# SW3203.net
KiCad netlist of a schematic drawn in Altium Designer
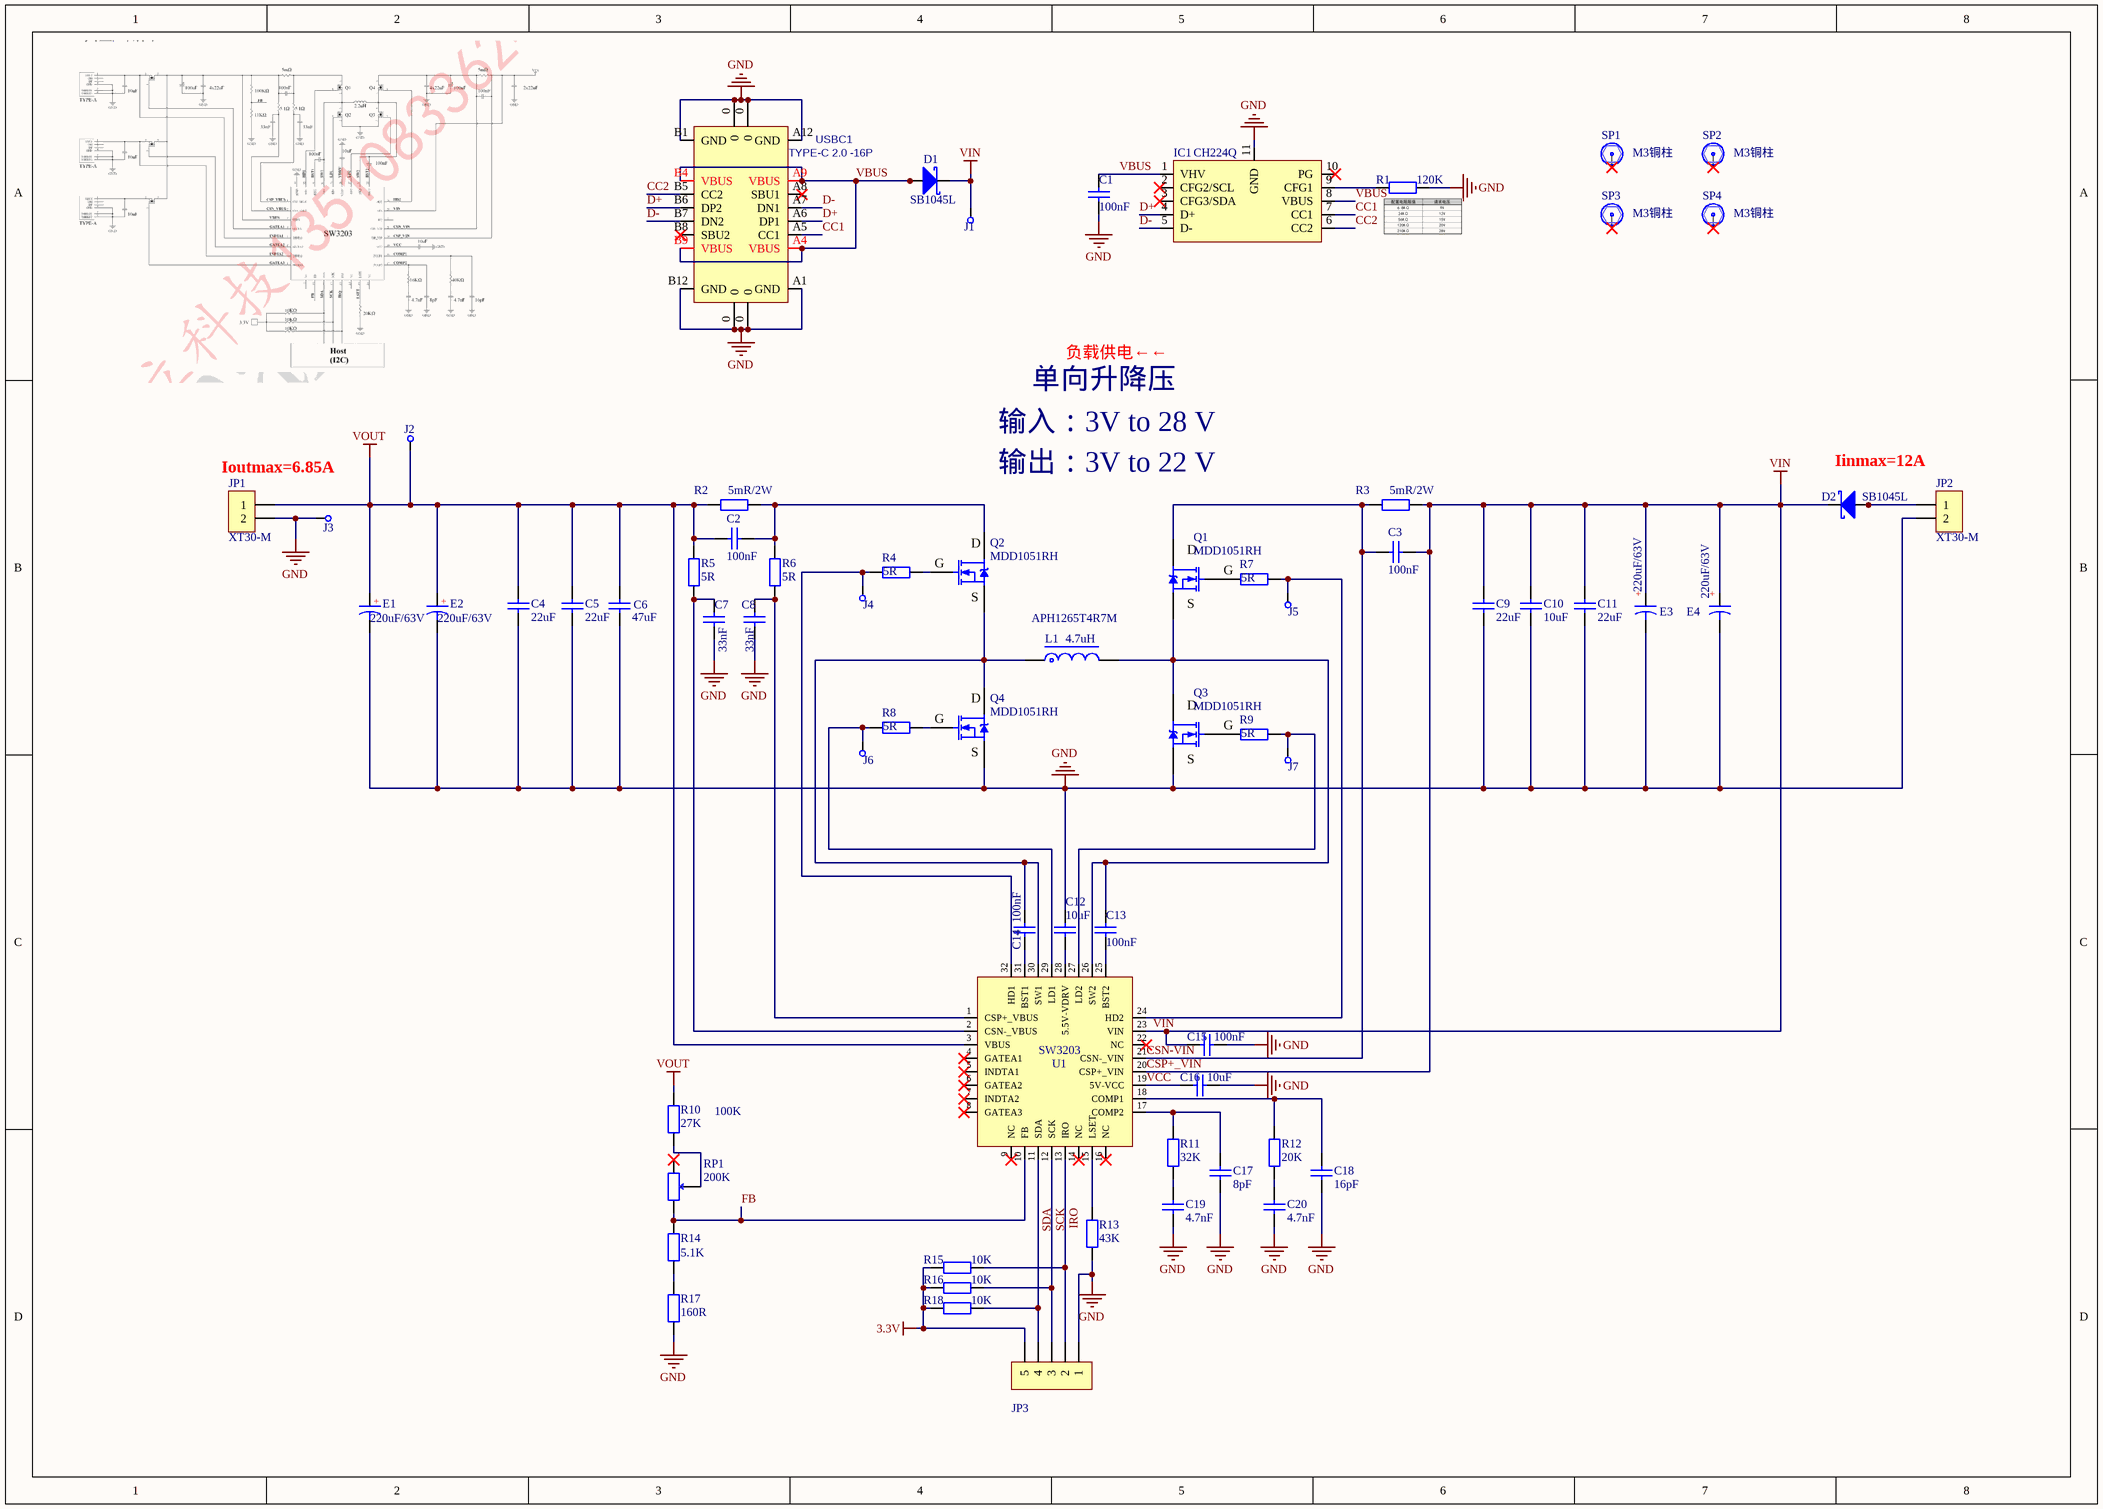
[diagram p0: SW3203.SchDoc]

(export (version "E")
  (design (tool "Eeschema 10.0.6"))
  (components
    (comp (ref "C1")
      (value "100nF")
      (footprint "C0805_L")
      (description "贴片电容/MLCC电容")
      (libsource (lib "0.1 - 电阻-电容-电感-保险丝-晶振-晶体-磁珠-电位器-法拉电容-馈通电容") (part "C"))
    )
    (comp (ref "C2")
      (value "100nF")
      (footprint "C0805_L")
      (description "贴片电容/MLCC电容")
      (libsource (lib "0.1 - 电阻-电容-电感-保险丝-晶振-晶体-磁珠-电位器-法拉电容-馈通电容") (part "C"))
    )
    (comp (ref "C3")
      (value "100nF")
      (footprint "C0805_L")
      (description "贴片电容/MLCC电容")
      (libsource (lib "0.1 - 电阻-电容-电感-保险丝-晶振-晶体-磁珠-电位器-法拉电容-馈通电容") (part "C"))
    )
    (comp (ref "C4")
      (value "22uF")
      (footprint "C0805_L")
      (description "贴片电容/MLCC电容")
      (libsource (lib "0.1 - 电阻-电容-电感-保险丝-晶振-晶体-磁珠-电位器-法拉电容-馈通电容") (part "C"))
    )
    (comp (ref "C5")
      (value "22uF")
      (footprint "C0805_L")
      (description "贴片电容/MLCC电容")
      (libsource (lib "0.1 - 电阻-电容-电感-保险丝-晶振-晶体-磁珠-电位器-法拉电容-馈通电容") (part "C"))
    )
    (comp (ref "C6")
      (value "47uF")
      (footprint "C0805_L")
      (description "贴片电容/MLCC电容")
      (libsource (lib "0.1 - 电阻-电容-电感-保险丝-晶振-晶体-磁珠-电位器-法拉电容-馈通电容") (part "C"))
    )
    (comp (ref "C7")
      (value "33nF")
      (footprint "C0805_L")
      (description "贴片电容/MLCC电容")
      (libsource (lib "0.1 - 电阻-电容-电感-保险丝-晶振-晶体-磁珠-电位器-法拉电容-馈通电容") (part "C"))
    )
    (comp (ref "C8")
      (value "33nF")
      (footprint "C0805_L")
      (description "贴片电容/MLCC电容")
      (libsource (lib "0.1 - 电阻-电容-电感-保险丝-晶振-晶体-磁珠-电位器-法拉电容-馈通电容") (part "C"))
    )
    (comp (ref "C9")
      (value "22uF")
      (footprint "C0805_L")
      (description "贴片电容/MLCC电容")
      (libsource (lib "0.1 - 电阻-电容-电感-保险丝-晶振-晶体-磁珠-电位器-法拉电容-馈通电容") (part "C"))
    )
    (comp (ref "C10")
      (value "10uF")
      (footprint "C0805_L")
      (description "贴片电容/MLCC电容")
      (libsource (lib "0.1 - 电阻-电容-电感-保险丝-晶振-晶体-磁珠-电位器-法拉电容-馈通电容") (part "C"))
    )
    (comp (ref "C11")
      (value "22uF")
      (footprint "C0805_L")
      (description "贴片电容/MLCC电容")
      (libsource (lib "0.1 - 电阻-电容-电感-保险丝-晶振-晶体-磁珠-电位器-法拉电容-馈通电容") (part "C"))
    )
    (comp (ref "C12")
      (value "10uF")
      (footprint "C0805_L")
      (description "贴片电容/MLCC电容")
      (libsource (lib "0.1 - 电阻-电容-电感-保险丝-晶振-晶体-磁珠-电位器-法拉电容-馈通电容") (part "C"))
    )
    (comp (ref "C13")
      (value "100nF")
      (footprint "C0805_L")
      (description "贴片电容/MLCC电容")
      (libsource (lib "0.1 - 电阻-电容-电感-保险丝-晶振-晶体-磁珠-电位器-法拉电容-馈通电容") (part "C"))
    )
    (comp (ref "C14")
      (value "100nF")
      (footprint "C0805_L")
      (description "贴片电容/MLCC电容")
      (libsource (lib "0.1 - 电阻-电容-电感-保险丝-晶振-晶体-磁珠-电位器-法拉电容-馈通电容") (part "C"))
    )
    (comp (ref "C15")
      (value "100nF")
      (footprint "C0805_L")
      (description "贴片电容/MLCC电容")
      (libsource (lib "0.1 - 电阻-电容-电感-保险丝-晶振-晶体-磁珠-电位器-法拉电容-馈通电容") (part "C"))
    )
    (comp (ref "C16")
      (value "10uF")
      (footprint "C0805_L")
      (description "贴片电容/MLCC电容")
      (libsource (lib "0.1 - 电阻-电容-电感-保险丝-晶振-晶体-磁珠-电位器-法拉电容-馈通电容") (part "C"))
    )
    (comp (ref "C17")
      (value "8pF")
      (footprint "C0805_L")
      (description "贴片电容/MLCC电容")
      (libsource (lib "0.1 - 电阻-电容-电感-保险丝-晶振-晶体-磁珠-电位器-法拉电容-馈通电容") (part "C"))
    )
    (comp (ref "C18")
      (value "16pF")
      (footprint "C0805_L")
      (description "贴片电容/MLCC电容")
      (libsource (lib "0.1 - 电阻-电容-电感-保险丝-晶振-晶体-磁珠-电位器-法拉电容-馈通电容") (part "C"))
    )
    (comp (ref "C19")
      (value "4.7nF")
      (footprint "C0805_L")
      (description "贴片电容/MLCC电容")
      (libsource (lib "0.1 - 电阻-电容-电感-保险丝-晶振-晶体-磁珠-电位器-法拉电容-馈通电容") (part "C"))
    )
    (comp (ref "C20")
      (value "4.7nF")
      (footprint "C0805_L")
      (description "贴片电容/MLCC电容")
      (libsource (lib "0.1 - 电阻-电容-电感-保险丝-晶振-晶体-磁珠-电位器-法拉电容-馈通电容") (part "C"))
    )
    (comp (ref "D1")
      (value "SB1045L")
      (footprint "TO-277_3P-L5.4-W4.0")
      (libsource (lib "0.2 - 二极管-TVS-ESD-整流桥-放电管") (part "SB1045L"))
    )
    (comp (ref "D2")
      (value "SB1045L")
      (footprint "TO-277_3P-L5.4-W4.0")
      (libsource (lib "0.2 - 二极管-TVS-ESD-整流桥-放电管") (part "SB1045L"))
    )
    (comp (ref "E1")
      (value "220uF/63V")
      (footprint "CT 5.0*10*13 - R")
      (description "直插固态电容")
      (libsource (lib "") (part "CS_1"))
    )
    (comp (ref "E2")
      (value "220uF/63V")
      (footprint "CT 5.0*10*13 - R")
      (description "直插固态电容")
      (libsource (lib "") (part "CS_1"))
    )
    (comp (ref "E3")
      (value "220uF/63V")
      (footprint "CT 5.0*10*13 - R")
      (description "直插固态电容")
      (libsource (lib "0.1 - 电阻-电容-电感-保险丝-晶振-晶体-磁珠-电位器-法拉电容-馈通电容") (part "CS"))
    )
    (comp (ref "E4")
      (value "220uF/63V")
      (footprint "CT 5.0*10*13 - R")
      (description "直插固态电容")
      (libsource (lib "0.1 - 电阻-电容-电感-保险丝-晶振-晶体-磁珠-电位器-法拉电容-馈通电容") (part "CS"))
    )
    (comp (ref "IC1")
      (value "CH224Q")
      (footprint "DFN-10_L2.0-W2")
      (libsource (lib "1.8 - CH340系列编程器芯片") (part "CH224Q"))
    )
    (comp (ref "J1")
      (value "CHECK")
      (footprint "CHECK-A")
      (description "测试点")
      (libsource (lib "课程库") (part "CHECK"))
    )
    (comp (ref "J2")
      (value "CHECK")
      (footprint "CHECK-A")
      (description "测试点")
      (libsource (lib "课程库") (part "CHECK"))
    )
    (comp (ref "J3")
      (value "CHECK")
      (footprint "CHECK-A")
      (description "测试点")
      (libsource (lib "课程库") (part "CHECK"))
    )
    (comp (ref "J4")
      (value "CHECK")
      (footprint "CHECK-A")
      (description "测试点")
      (libsource (lib "课程库") (part "CHECK"))
    )
    (comp (ref "J5")
      (value "CHECK")
      (footprint "CHECK-A")
      (description "测试点")
      (libsource (lib "课程库") (part "CHECK"))
    )
    (comp (ref "J6")
      (value "CHECK")
      (footprint "CHECK-A")
      (description "测试点")
      (libsource (lib "课程库") (part "CHECK"))
    )
    (comp (ref "J7")
      (value "CHECK")
      (footprint "CHECK-A")
      (description "测试点")
      (libsource (lib "课程库") (part "CHECK"))
    )
    (comp (ref "JP1")
      (value "XT30-M")
      (footprint "XT30PW-M")
      (description "XT30公头")
      (libsource (lib "") (part "XT30-M_1"))
    )
    (comp (ref "JP2")
      (value "XT30-M")
      (footprint "XT30PW-M")
      (description "XT30公头")
      (libsource (lib "0.6 - 电源_音频_USB Type-C_HDMI_XT60_5557_D-SUB_RJ45_SD-TF_SIM插座") (part "XT30-M"))
    )
    (comp (ref "JP3")
      (value "HDR-1X5")
      (footprint "HDR2.54-M-LI-5P")
      (description "5P接插件")
      (libsource (lib "5.5 - 2.54mm连接器(KF2EDGK_XH2.54_2.54排针排母)") (part "Header 5"))
    )
    (comp (ref "L1")
      (value "4.7uH")
      (footprint "SMD,13.5x12.6mm")
      (description "一体成型电感")
      (libsource (lib "0.1 - 电阻-电容-电感-保险丝-晶振-晶体-磁珠-电位器-法拉电容-馈通电容") (part "L-Molding Choke"))
    )
    (comp (ref "Q1")
      (value "MDD1051RH")
      (footprint "TO252")
      (description "N沟道 30V/80A")
      (libsource (lib "0.4 - 三极管-场效应管-可控硅") (part "NCE3080"))
    )
    (comp (ref "Q2")
      (value "MDD1051RH")
      (footprint "TO252")
      (description "N沟道 30V/80A")
      (libsource (lib "0.4 - 三极管-场效应管-可控硅") (part "NCE3080"))
    )
    (comp (ref "Q3")
      (value "MDD1051RH")
      (footprint "TO252")
      (description "N沟道 30V/80A")
      (libsource (lib "0.4 - 三极管-场效应管-可控硅") (part "NCE3080"))
    )
    (comp (ref "Q4")
      (value "MDD1051RH")
      (footprint "TO252")
      (description "N沟道 30V/80A")
      (libsource (lib "0.4 - 三极管-场效应管-可控硅") (part "NCE3080"))
    )
    (comp (ref "R1")
      (value "120K")
      (footprint "R0805_L")
      (description "贴片电阻")
      (libsource (lib "0.1 - 电阻-电容-电感-保险丝-晶振-晶体-磁珠-电位器-法拉电容-馈通电容") (part "R"))
    )
    (comp (ref "R2")
      (value "5mR/2W")
      (footprint "R2512_M")
      (description "贴片电阻")
      (libsource (lib "0.1 - 电阻-电容-电感-保险丝-晶振-晶体-磁珠-电位器-法拉电容-馈通电容") (part "R"))
    )
    (comp (ref "R3")
      (value "5mR/2W")
      (footprint "R2512_M")
      (description "贴片电阻")
      (libsource (lib "0.1 - 电阻-电容-电感-保险丝-晶振-晶体-磁珠-电位器-法拉电容-馈通电容") (part "R"))
    )
    (comp (ref "R4")
      (value "5R")
      (footprint "R0805_L")
      (description "贴片电阻")
      (libsource (lib "0.1 - 电阻-电容-电感-保险丝-晶振-晶体-磁珠-电位器-法拉电容-馈通电容") (part "R"))
    )
    (comp (ref "R5")
      (value "5R")
      (footprint "R0805_L")
      (description "贴片电阻")
      (libsource (lib "0.1 - 电阻-电容-电感-保险丝-晶振-晶体-磁珠-电位器-法拉电容-馈通电容") (part "R"))
    )
    (comp (ref "R6")
      (value "5R")
      (footprint "R0805_L")
      (description "贴片电阻")
      (libsource (lib "0.1 - 电阻-电容-电感-保险丝-晶振-晶体-磁珠-电位器-法拉电容-馈通电容") (part "R"))
    )
    (comp (ref "R7")
      (value "5R")
      (footprint "R0805_L")
      (description "贴片电阻")
      (libsource (lib "0.1 - 电阻-电容-电感-保险丝-晶振-晶体-磁珠-电位器-法拉电容-馈通电容") (part "R"))
    )
    (comp (ref "R8")
      (value "5R")
      (footprint "R0805_L")
      (description "贴片电阻")
      (libsource (lib "0.1 - 电阻-电容-电感-保险丝-晶振-晶体-磁珠-电位器-法拉电容-馈通电容") (part "R"))
    )
    (comp (ref "R9")
      (value "5R")
      (footprint "R0805_L")
      (description "贴片电阻")
      (libsource (lib "0.1 - 电阻-电容-电感-保险丝-晶振-晶体-磁珠-电位器-法拉电容-馈通电容") (part "R"))
    )
    (comp (ref "R10")
      (value "27K")
      (footprint "R0805_L")
      (description "贴片电阻")
      (libsource (lib "0.1 - 电阻-电容-电感-保险丝-晶振-晶体-磁珠-电位器-法拉电容-馈通电容") (part "R"))
    )
    (comp (ref "R11")
      (value "32K")
      (footprint "R0805_L")
      (description "贴片电阻")
      (libsource (lib "0.1 - 电阻-电容-电感-保险丝-晶振-晶体-磁珠-电位器-法拉电容-馈通电容") (part "R"))
    )
    (comp (ref "R12")
      (value "20K")
      (footprint "R0805_L")
      (description "贴片电阻")
      (libsource (lib "0.1 - 电阻-电容-电感-保险丝-晶振-晶体-磁珠-电位器-法拉电容-馈通电容") (part "R"))
    )
    (comp (ref "R13")
      (value "43K")
      (footprint "R0805_L")
      (description "贴片电阻")
      (libsource (lib "0.1 - 电阻-电容-电感-保险丝-晶振-晶体-磁珠-电位器-法拉电容-馈通电容") (part "R"))
    )
    (comp (ref "R14")
      (value "5.1K")
      (footprint "R0805_L")
      (description "贴片电阻")
      (libsource (lib "0.1 - 电阻-电容-电感-保险丝-晶振-晶体-磁珠-电位器-法拉电容-馈通电容") (part "R"))
    )
    (comp (ref "R15")
      (value "10K")
      (footprint "R0805_L")
      (description "贴片电阻")
      (libsource (lib "0.1 - 电阻-电容-电感-保险丝-晶振-晶体-磁珠-电位器-法拉电容-馈通电容") (part "R"))
    )
    (comp (ref "R16")
      (value "10K")
      (footprint "R0805_L")
      (description "贴片电阻")
      (libsource (lib "0.1 - 电阻-电容-电感-保险丝-晶振-晶体-磁珠-电位器-法拉电容-馈通电容") (part "R"))
    )
    (comp (ref "R17")
      (value "160R")
      (footprint "R0805_L")
      (description "贴片电阻")
      (libsource (lib "0.1 - 电阻-电容-电感-保险丝-晶振-晶体-磁珠-电位器-法拉电容-馈通电容") (part "R"))
    )
    (comp (ref "R18")
      (value "10K")
      (footprint "R0805_L")
      (description "贴片电阻")
      (libsource (lib "0.1 - 电阻-电容-电感-保险丝-晶振-晶体-磁珠-电位器-法拉电容-馈通电容") (part "R"))
    )
    (comp (ref "RP1")
      (value "200K")
      (footprint "3296W")
      (description "单联电位器")
      (libsource (lib "0.1 - 电阻-电容-电感-保险丝-晶振-晶体-磁珠-电位器-法拉电容-馈通电容") (part "RP"))
    )
    (comp (ref "SP1")
      (value "M3铜柱")
      (footprint "M3x4_L")
      (description "铜柱")
      (libsource (lib "0.5 - 按键_开关_蜂鸣器_电池_测试点_Mark点_铜柱") (part "铜柱小焊盘"))
    )
    (comp (ref "SP2")
      (value "M3铜柱")
      (footprint "M3x4_L")
      (description "铜柱")
      (libsource (lib "0.5 - 按键_开关_蜂鸣器_电池_测试点_Mark点_铜柱") (part "铜柱小焊盘"))
    )
    (comp (ref "SP3")
      (value "M3铜柱")
      (footprint "M3x4_L")
      (description "铜柱")
      (libsource (lib "0.5 - 按键_开关_蜂鸣器_电池_测试点_Mark点_铜柱") (part "铜柱小焊盘"))
    )
    (comp (ref "SP4")
      (value "M3铜柱")
      (footprint "M3x4_L")
      (description "铜柱")
      (libsource (lib "0.5 - 按键_开关_蜂鸣器_电池_测试点_Mark点_铜柱") (part "铜柱小焊盘"))
    )
    (comp (ref "U1")
      (value "SW3203")
      (footprint "QFN32_L4.0-W4.0-P0.4")
      (description "3~28V同步 4 管升降压控制器")
      (libsource (lib "0.7 - 电源类芯片") (part "SW3203"))
    )
    (comp (ref "USBC1")
      (value "TYPE-C 2.0 -16P")
      (footprint "USB-C-SMD_16P")
      (description "USB2.0_Type-C_16Pin母座")
      (libsource (lib "0.6 - 电源_音频_USB Type-C_HDMI_XT60_5557_D-SUB_RJ45_SD-TF_SIM插座") (part "USB2.0_Type-C_16Pin"))
    )
  )
  (nets
    (net (code "1") (name "/CC1") (class "Default")
      (node (ref "IC1") (pin "7") (pinfunction "CC1_7") (pintype "passive"))
      (node (ref "USBC1") (pin "A5") (pinfunction "CC1_A5") (pintype "passive"))
    )
    (net (code "2") (name "/CC2") (class "Default")
      (node (ref "IC1") (pin "6") (pinfunction "CC2_6") (pintype "passive"))
      (node (ref "USBC1") (pin "B5") (pinfunction "CC2_B5") (pintype "passive"))
    )
    (net (code "3") (name "/CSN-VIN") (class "Default")
      (node (ref "C3") (pin "2") (pinfunction "2_2") (pintype "passive"))
      (node (ref "Q1") (pin "2") (pinfunction "D_2") (pintype "passive"))
      (node (ref "R3") (pin "2") (pinfunction "2_2") (pintype "passive"))
      (node (ref "U1") (pin "21") (pinfunction "CSN-_VIN_21") (pintype "passive"))
    )
    (net (code "4") (name "/D+") (class "Default")
      (node (ref "IC1") (pin "4") (pinfunction "D+_4") (pintype "passive"))
      (node (ref "USBC1") (pin "A6") (pinfunction "DP1_A6") (pintype "passive"))
      (node (ref "USBC1") (pin "B6") (pinfunction "DP2_B6") (pintype "passive"))
    )
    (net (code "5") (name "/D-") (class "Default")
      (node (ref "IC1") (pin "5") (pinfunction "D-_5") (pintype "passive"))
      (node (ref "USBC1") (pin "A7") (pinfunction "DN1_A7") (pintype "passive"))
      (node (ref "USBC1") (pin "B7") (pinfunction "DN2_B7") (pintype "passive"))
    )
    (net (code "6") (name "/FB") (class "Default")
      (node (ref "R14") (pin "1") (pinfunction "1_1") (pintype "passive"))
      (node (ref "RP1") (pin "1") (pinfunction "1_1") (pintype "passive"))
      (node (ref "U1") (pin "10") (pinfunction "FB_10") (pintype "passive"))
    )
    (net (code "7") (name "/IRO") (class "Default")
      (node (ref "JP3") (pin "2") (pinfunction "2_2") (pintype "passive"))
      (node (ref "R15") (pin "2") (pinfunction "2_2") (pintype "passive"))
      (node (ref "U1") (pin "13") (pinfunction "IRO_13") (pintype "passive"))
    )
    (net (code "8") (name "/SCK") (class "Default")
      (node (ref "JP3") (pin "3") (pinfunction "3_3") (pintype "passive"))
      (node (ref "R16") (pin "2") (pinfunction "2_2") (pintype "passive"))
      (node (ref "U1") (pin "12") (pinfunction "SCK_12") (pintype "passive"))
    )
    (net (code "9") (name "/SDA") (class "Default")
      (node (ref "JP3") (pin "4") (pinfunction "4_4") (pintype "passive"))
      (node (ref "R18") (pin "2") (pinfunction "2_2") (pintype "passive"))
      (node (ref "U1") (pin "11") (pinfunction "SDA_11") (pintype "passive"))
    )
    (net (code "10") (name "/VBUS") (class "Default")
      (node (ref "C1") (pin "2") (pinfunction "2_2") (pintype "passive"))
      (node (ref "D1") (pin "1") (pinfunction "A_1") (pintype "passive"))
      (node (ref "D1") (pin "3") (pinfunction "A_3") (pintype "passive"))
      (node (ref "IC1") (pin "1") (pinfunction "VHV_1") (pintype "passive"))
      (node (ref "IC1") (pin "8") (pinfunction "VBUS_8") (pintype "passive"))
      (node (ref "USBC1") (pin "A4") (pinfunction "VBUS_A4") (pintype "passive"))
      (node (ref "USBC1") (pin "A9") (pinfunction "VBUS_A9") (pintype "passive"))
      (node (ref "USBC1") (pin "B4") (pinfunction "VBUS_B4") (pintype "passive"))
      (node (ref "USBC1") (pin "B9") (pinfunction "VBUS_B9") (pintype "passive"))
    )
    (net (code "11") (name "/VCC") (class "Default")
      (node (ref "C16") (pin "2") (pinfunction "2_2") (pintype "passive"))
      (node (ref "U1") (pin "19") (pinfunction "5V-VCC_19") (pintype "passive"))
    )
    (net (code "12") (name "3.3V") (class "Default")
      (node (ref "JP3") (pin "5") (pinfunction "5_5") (pintype "passive"))
      (node (ref "R15") (pin "1") (pinfunction "1_1") (pintype "passive"))
      (node (ref "R16") (pin "1") (pinfunction "1_1") (pintype "passive"))
      (node (ref "R18") (pin "1") (pinfunction "1_1") (pintype "passive"))
    )
    (net (code "13") (name "GND") (class "Default")
      (node (ref "C1") (pin "1") (pinfunction "1_1") (pintype "passive"))
      (node (ref "C10") (pin "1") (pinfunction "1_1") (pintype "passive"))
      (node (ref "C11") (pin "1") (pinfunction "1_1") (pintype "passive"))
      (node (ref "C12") (pin "2") (pinfunction "2_2") (pintype "passive"))
      (node (ref "C15") (pin "1") (pinfunction "1_1") (pintype "passive"))
      (node (ref "C16") (pin "1") (pinfunction "1_1") (pintype "passive"))
      (node (ref "C17") (pin "1") (pinfunction "1_1") (pintype "passive"))
      (node (ref "C18") (pin "1") (pinfunction "1_1") (pintype "passive"))
      (node (ref "C19") (pin "1") (pinfunction "1_1") (pintype "passive"))
      (node (ref "C20") (pin "1") (pinfunction "1_1") (pintype "passive"))
      (node (ref "C4") (pin "1") (pinfunction "1_1") (pintype "passive"))
      (node (ref "C5") (pin "1") (pinfunction "1_1") (pintype "passive"))
      (node (ref "C6") (pin "1") (pinfunction "1_1") (pintype "passive"))
      (node (ref "C7") (pin "2") (pinfunction "2_2") (pintype "passive"))
      (node (ref "C8") (pin "2") (pinfunction "2_2") (pintype "passive"))
      (node (ref "C9") (pin "1") (pinfunction "1_1") (pintype "passive"))
      (node (ref "E1") (pin "2") (pinfunction "2_2") (pintype "passive"))
      (node (ref "E2") (pin "2") (pinfunction "2_2") (pintype "passive"))
      (node (ref "E3") (pin "2") (pinfunction "2_2") (pintype "passive"))
      (node (ref "E4") (pin "2") (pinfunction "2_2") (pintype "passive"))
      (node (ref "IC1") (pin "11") (pinfunction "GND_11") (pintype "passive"))
      (node (ref "J3") (pin "1") (pinfunction "1_1") (pintype "passive"))
      (node (ref "JP1") (pin "2") (pinfunction "2_2") (pintype "passive"))
      (node (ref "JP2") (pin "2") (pinfunction "2_2") (pintype "passive"))
      (node (ref "JP3") (pin "1") (pinfunction "1_1") (pintype "passive"))
      (node (ref "Q3") (pin "3") (pinfunction "S_3") (pintype "passive"))
      (node (ref "Q4") (pin "3") (pinfunction "S_3") (pintype "passive"))
      (node (ref "R1") (pin "2") (pinfunction "2_2") (pintype "passive"))
      (node (ref "R13") (pin "2") (pinfunction "2_2") (pintype "passive"))
      (node (ref "R17") (pin "2") (pinfunction "2_2") (pintype "passive"))
      (node (ref "USBC1") (pin "0") (pinfunction "0_0") (pintype "passive"))
      (node (ref "USBC1") (pin "A1") (pinfunction "GND_A1") (pintype "passive"))
      (node (ref "USBC1") (pin "A12") (pinfunction "GND_A12") (pintype "passive"))
      (node (ref "USBC1") (pin "B1") (pinfunction "GND_B1") (pintype "passive"))
      (node (ref "USBC1") (pin "B12") (pinfunction "GND_B12") (pintype "passive"))
    )
    (net (code "14") (name "Net-(C19-Pad2)") (class "Default")
      (node (ref "C19") (pin "2") (pinfunction "2_2") (pintype "passive"))
      (node (ref "R11") (pin "2") (pinfunction "2_2") (pintype "passive"))
    )
    (net (code "15") (name "Net-(C20-Pad2)") (class "Default")
      (node (ref "C20") (pin "2") (pinfunction "2_2") (pintype "passive"))
      (node (ref "R12") (pin "2") (pinfunction "2_2") (pintype "passive"))
    )
    (net (code "16") (name "Net-(D2-A-Pad1)") (class "Default")
      (node (ref "D2") (pin "1") (pinfunction "A_1") (pintype "passive"))
      (node (ref "D2") (pin "3") (pinfunction "A_3") (pintype "passive"))
      (node (ref "JP2") (pin "1") (pinfunction "1_1") (pintype "passive"))
    )
    (net (code "17") (name "Net-(IC1-CFG1)") (class "Default")
      (node (ref "IC1") (pin "9") (pinfunction "CFG1_9") (pintype "passive"))
      (node (ref "R1") (pin "1") (pinfunction "1_1") (pintype "passive"))
    )
    (net (code "18") (name "Net-(Q1-G)") (class "Default")
      (node (ref "Q1") (pin "1") (pinfunction "G_1") (pintype "passive"))
      (node (ref "R7") (pin "2") (pinfunction "2_2") (pintype "passive"))
    )
    (net (code "19") (name "Net-(Q1-S)") (class "Default")
      (node (ref "C13") (pin "2") (pinfunction "2_2") (pintype "passive"))
      (node (ref "L1") (pin "2") (pinfunction "2_2") (pintype "passive"))
      (node (ref "Q1") (pin "3") (pinfunction "S_3") (pintype "passive"))
      (node (ref "Q3") (pin "2") (pinfunction "D_2") (pintype "passive"))
      (node (ref "U1") (pin "26") (pinfunction "SW2_26") (pintype "passive"))
    )
    (net (code "20") (name "Net-(Q2-D)") (class "Default")
      (node (ref "C2") (pin "1") (pinfunction "1_1") (pintype "passive"))
      (node (ref "Q2") (pin "2") (pinfunction "D_2") (pintype "passive"))
      (node (ref "R2") (pin "1") (pinfunction "1_1") (pintype "passive"))
      (node (ref "R6") (pin "1") (pinfunction "1_1") (pintype "passive"))
    )
    (net (code "21") (name "Net-(Q2-G)") (class "Default")
      (node (ref "Q2") (pin "1") (pinfunction "G_1") (pintype "passive"))
      (node (ref "R4") (pin "1") (pinfunction "1_1") (pintype "passive"))
    )
    (net (code "22") (name "Net-(Q2-S)") (class "Default")
      (node (ref "C14") (pin "2") (pinfunction "2_2") (pintype "passive"))
      (node (ref "L1") (pin "1") (pinfunction "1_1") (pintype "passive"))
      (node (ref "Q2") (pin "3") (pinfunction "S_3") (pintype "passive"))
      (node (ref "Q4") (pin "2") (pinfunction "D_2") (pintype "passive"))
      (node (ref "U1") (pin "30") (pinfunction "SW1_30") (pintype "passive"))
    )
    (net (code "23") (name "Net-(Q3-G)") (class "Default")
      (node (ref "Q3") (pin "1") (pinfunction "G_1") (pintype "passive"))
      (node (ref "R9") (pin "2") (pinfunction "2_2") (pintype "passive"))
    )
    (net (code "24") (name "Net-(Q4-G)") (class "Default")
      (node (ref "Q4") (pin "1") (pinfunction "G_1") (pintype "passive"))
      (node (ref "R8") (pin "1") (pinfunction "1_1") (pintype "passive"))
    )
    (net (code "25") (name "Net-(R10-Pad2)") (class "Default")
      (node (ref "R10") (pin "2") (pinfunction "2_2") (pintype "passive"))
      (node (ref "RP1") (pin "2") (pinfunction "2_2") (pintype "passive"))
    )
    (net (code "26") (name "Net-(R14-Pad2)") (class "Default")
      (node (ref "R14") (pin "2") (pinfunction "2_2") (pintype "passive"))
      (node (ref "R17") (pin "1") (pinfunction "1_1") (pintype "passive"))
    )
    (net (code "27") (name "Net-(U1-5.5V-VDRV)") (class "Default")
      (node (ref "C12") (pin "1") (pinfunction "1_1") (pintype "passive"))
      (node (ref "U1") (pin "28") (pinfunction "5.5V-VDRV_28") (pintype "passive"))
    )
    (net (code "28") (name "Net-(U1-BST1)") (class "Default")
      (node (ref "C14") (pin "1") (pinfunction "1_1") (pintype "passive"))
      (node (ref "U1") (pin "31") (pinfunction "BST1_31") (pintype "passive"))
    )
    (net (code "29") (name "Net-(U1-BST2)") (class "Default")
      (node (ref "C13") (pin "1") (pinfunction "1_1") (pintype "passive"))
      (node (ref "U1") (pin "25") (pinfunction "BST2_25") (pintype "passive"))
    )
    (net (code "30") (name "Net-(U1-COMP1)") (class "Default")
      (node (ref "C18") (pin "2") (pinfunction "2_2") (pintype "passive"))
      (node (ref "R12") (pin "1") (pinfunction "1_1") (pintype "passive"))
      (node (ref "U1") (pin "18") (pinfunction "COMP1_18") (pintype "passive"))
    )
    (net (code "31") (name "Net-(U1-COMP2)") (class "Default")
      (node (ref "C17") (pin "2") (pinfunction "2_2") (pintype "passive"))
      (node (ref "R11") (pin "1") (pinfunction "1_1") (pintype "passive"))
      (node (ref "U1") (pin "17") (pinfunction "COMP2_17") (pintype "passive"))
    )
    (net (code "32") (name "Net-(U1-CSN-_VBUS)") (class "Default")
      (node (ref "C7") (pin "1") (pinfunction "1_1") (pintype "passive"))
      (node (ref "R5") (pin "2") (pinfunction "2_2") (pintype "passive"))
      (node (ref "U1") (pin "2") (pinfunction "CSN-_VBUS_2") (pintype "passive"))
    )
    (net (code "33") (name "Net-(U1-CSP+_VBUS)") (class "Default")
      (node (ref "C8") (pin "1") (pinfunction "1_1") (pintype "passive"))
      (node (ref "R6") (pin "2") (pinfunction "2_2") (pintype "passive"))
      (node (ref "U1") (pin "1") (pinfunction "CSP+_VBUS_1") (pintype "passive"))
    )
    (net (code "34") (name "Net-(U1-HD1)") (class "Default")
      (node (ref "J4") (pin "1") (pinfunction "1_1") (pintype "passive"))
      (node (ref "R4") (pin "2") (pinfunction "2_2") (pintype "passive"))
      (node (ref "U1") (pin "32") (pinfunction "HD1_32") (pintype "passive"))
    )
    (net (code "35") (name "Net-(U1-HD2)") (class "Default")
      (node (ref "J5") (pin "1") (pinfunction "1_1") (pintype "passive"))
      (node (ref "R7") (pin "1") (pinfunction "1_1") (pintype "passive"))
      (node (ref "U1") (pin "24") (pinfunction "HD2_24") (pintype "passive"))
    )
    (net (code "36") (name "Net-(U1-LD1)") (class "Default")
      (node (ref "J6") (pin "1") (pinfunction "1_1") (pintype "passive"))
      (node (ref "R8") (pin "2") (pinfunction "2_2") (pintype "passive"))
      (node (ref "U1") (pin "29") (pinfunction "LD1_29") (pintype "passive"))
    )
    (net (code "37") (name "Net-(U1-LD2)") (class "Default")
      (node (ref "J7") (pin "1") (pinfunction "1_1") (pintype "passive"))
      (node (ref "R9") (pin "1") (pinfunction "1_1") (pintype "passive"))
      (node (ref "U1") (pin "27") (pinfunction "LD2_27") (pintype "passive"))
    )
    (net (code "38") (name "Net-(U1-LSET)") (class "Default")
      (node (ref "R13") (pin "1") (pinfunction "1_1") (pintype "passive"))
      (node (ref "U1") (pin "15") (pinfunction "LSET_15") (pintype "passive"))
    )
    (net (code "39") (name "VIN") (class "Default")
      (node (ref "C10") (pin "2") (pinfunction "2_2") (pintype "passive"))
      (node (ref "C11") (pin "2") (pinfunction "2_2") (pintype "passive"))
      (node (ref "C15") (pin "2") (pinfunction "2_2") (pintype "passive"))
      (node (ref "C3") (pin "1") (pinfunction "1_1") (pintype "passive"))
      (node (ref "C9") (pin "2") (pinfunction "2_2") (pintype "passive"))
      (node (ref "D1") (pin "2") (pinfunction "K_2") (pintype "passive"))
      (node (ref "D2") (pin "2") (pinfunction "K_2") (pintype "passive"))
      (node (ref "E3") (pin "1") (pinfunction "1_1") (pintype "passive"))
      (node (ref "E4") (pin "1") (pinfunction "1_1") (pintype "passive"))
      (node (ref "J1") (pin "1") (pinfunction "1_1") (pintype "passive"))
      (node (ref "R3") (pin "1") (pinfunction "1_1") (pintype "passive"))
      (node (ref "U1") (pin "20") (pinfunction "CSP+_VIN_20") (pintype "passive"))
      (node (ref "U1") (pin "23") (pinfunction "VIN_23") (pintype "passive"))
    )
    (net (code "40") (name "VOUT") (class "Default")
      (node (ref "C2") (pin "2") (pinfunction "2_2") (pintype "passive"))
      (node (ref "C4") (pin "2") (pinfunction "2_2") (pintype "passive"))
      (node (ref "C5") (pin "2") (pinfunction "2_2") (pintype "passive"))
      (node (ref "C6") (pin "2") (pinfunction "2_2") (pintype "passive"))
      (node (ref "E1") (pin "1") (pinfunction "1_1") (pintype "passive"))
      (node (ref "E2") (pin "1") (pinfunction "1_1") (pintype "passive"))
      (node (ref "J2") (pin "1") (pinfunction "1_1") (pintype "passive"))
      (node (ref "JP1") (pin "1") (pinfunction "1_1") (pintype "passive"))
      (node (ref "R10") (pin "1") (pinfunction "1_1") (pintype "passive"))
      (node (ref "R2") (pin "2") (pinfunction "2_2") (pintype "passive"))
      (node (ref "R5") (pin "1") (pinfunction "1_1") (pintype "passive"))
      (node (ref "U1") (pin "3") (pinfunction "VBUS_3") (pintype "passive"))
    )
    (net (code "41") (name "unconnected-(IC1-CFG2{slash}SCL-Pad2)") (class "Default")
      (node (ref "IC1") (pin "2") (pinfunction "CFG2/SCL_2") (pintype "passive+no_connect"))
    )
    (net (code "42") (name "unconnected-(IC1-CFG3{slash}SDA-Pad3)") (class "Default")
      (node (ref "IC1") (pin "3") (pinfunction "CFG3/SDA_3") (pintype "passive+no_connect"))
    )
    (net (code "43") (name "unconnected-(IC1-PG-Pad10)") (class "Default")
      (node (ref "IC1") (pin "10") (pinfunction "PG_10") (pintype "passive+no_connect"))
    )
    (net (code "44") (name "unconnected-(RP1-Pad3)") (class "Default")
      (node (ref "RP1") (pin "3") (pinfunction "3_3") (pintype "passive+no_connect"))
    )
    (net (code "45") (name "unconnected-(SP1-Pad1)") (class "Default")
      (node (ref "SP1") (pin "1") (pinfunction "1_1") (pintype "passive+no_connect"))
    )
    (net (code "46") (name "unconnected-(SP2-Pad1)") (class "Default")
      (node (ref "SP2") (pin "1") (pinfunction "1_1") (pintype "passive+no_connect"))
    )
    (net (code "47") (name "unconnected-(SP3-Pad1)") (class "Default")
      (node (ref "SP3") (pin "1") (pinfunction "1_1") (pintype "passive+no_connect"))
    )
    (net (code "48") (name "unconnected-(SP4-Pad1)") (class "Default")
      (node (ref "SP4") (pin "1") (pinfunction "1_1") (pintype "passive+no_connect"))
    )
    (net (code "49") (name "unconnected-(U1-GATEA1-Pad4)") (class "Default")
      (node (ref "U1") (pin "4") (pinfunction "GATEA1_4") (pintype "passive+no_connect"))
    )
    (net (code "50") (name "unconnected-(U1-GATEA2-Pad6)") (class "Default")
      (node (ref "U1") (pin "6") (pinfunction "GATEA2_6") (pintype "passive+no_connect"))
    )
    (net (code "51") (name "unconnected-(U1-GATEA3-Pad8)") (class "Default")
      (node (ref "U1") (pin "8") (pinfunction "GATEA3_8") (pintype "passive+no_connect"))
    )
    (net (code "52") (name "unconnected-(U1-INDTA1-Pad5)") (class "Default")
      (node (ref "U1") (pin "5") (pinfunction "INDTA1_5") (pintype "passive+no_connect"))
    )
    (net (code "53") (name "unconnected-(U1-INDTA2-Pad7)") (class "Default")
      (node (ref "U1") (pin "7") (pinfunction "INDTA2_7") (pintype "passive+no_connect"))
    )
    (net (code "54") (name "unconnected-(U1-NC-Pad9)") (class "Default")
      (node (ref "U1") (pin "9") (pinfunction "NC_9") (pintype "passive+no_connect"))
    )
    (net (code "55") (name "unconnected-(U1-NC-Pad14)") (class "Default")
      (node (ref "U1") (pin "14") (pinfunction "NC_14") (pintype "passive+no_connect"))
    )
    (net (code "56") (name "unconnected-(U1-NC-Pad16)") (class "Default")
      (node (ref "U1") (pin "16") (pinfunction "NC_16") (pintype "passive+no_connect"))
    )
    (net (code "57") (name "unconnected-(U1-NC-Pad22)") (class "Default")
      (node (ref "U1") (pin "22") (pinfunction "NC_22") (pintype "passive+no_connect"))
    )
    (net (code "58") (name "unconnected-(USBC1-SBU1-PadA8)") (class "Default")
      (node (ref "USBC1") (pin "A8") (pinfunction "SBU1_A8") (pintype "passive+no_connect"))
    )
    (net (code "59") (name "unconnected-(USBC1-SBU2-PadB8)") (class "Default")
      (node (ref "USBC1") (pin "B8") (pinfunction "SBU2_B8") (pintype "passive+no_connect"))
    )
  )
)
